# Sch_Kur.net
KiCad netlist of a schematic drawn in Altium Designer
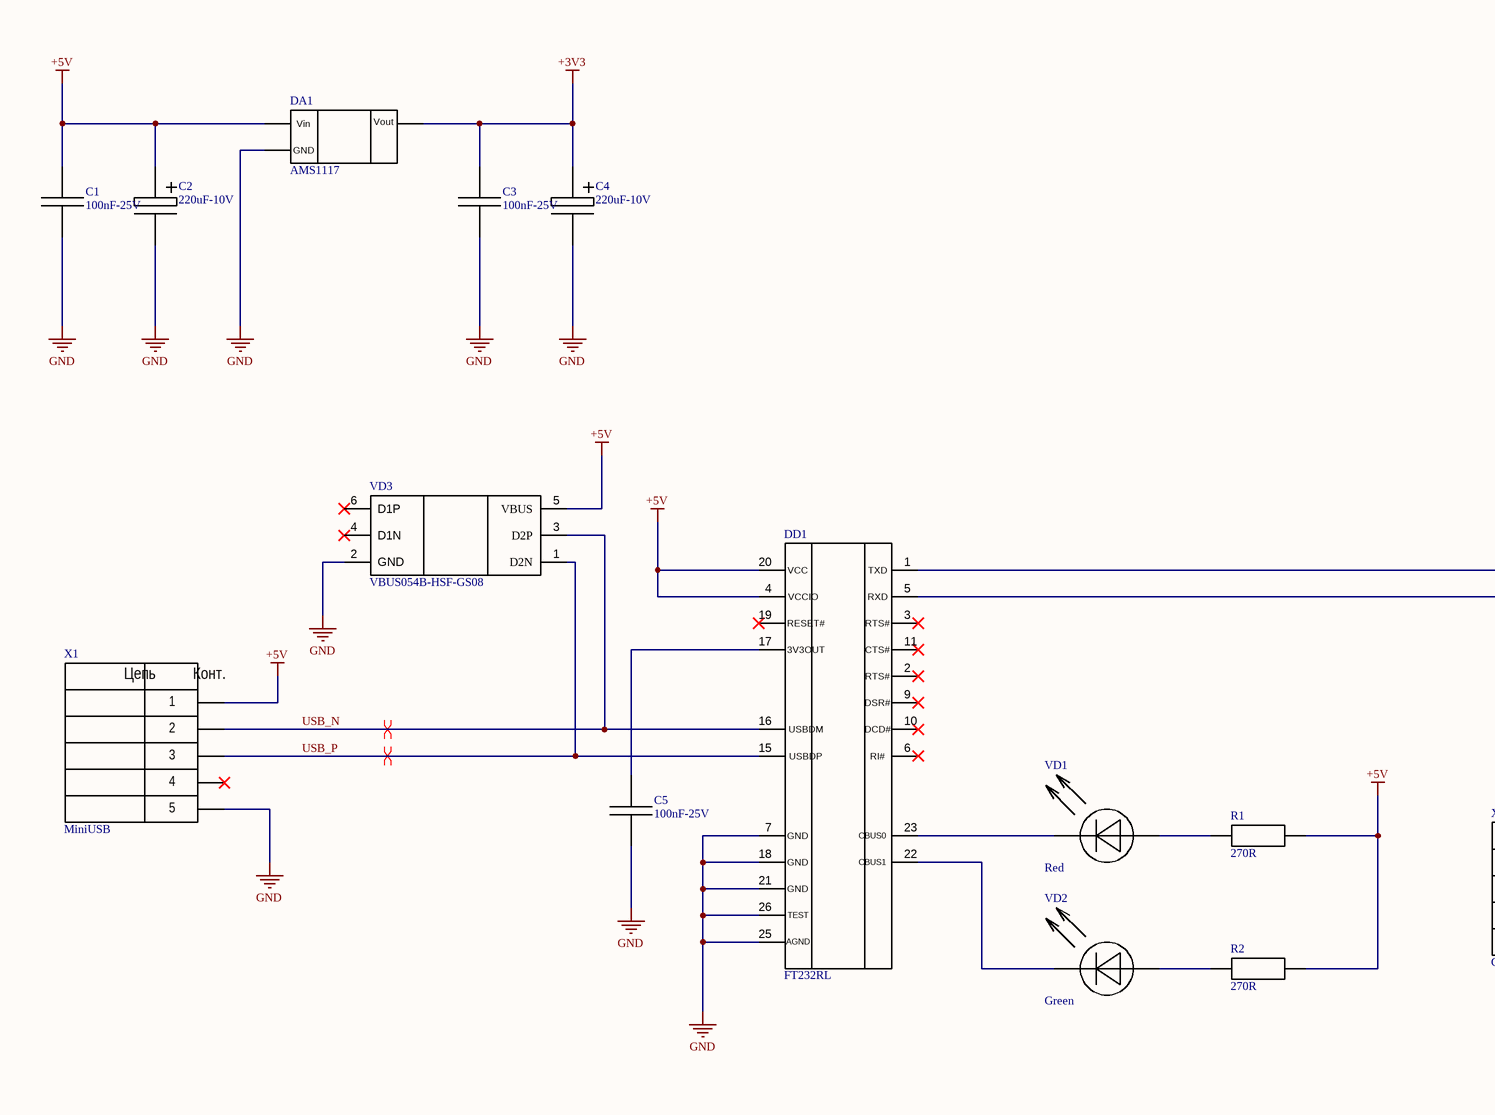
[diagram p0: Sch_Kur.SchDoc, left]
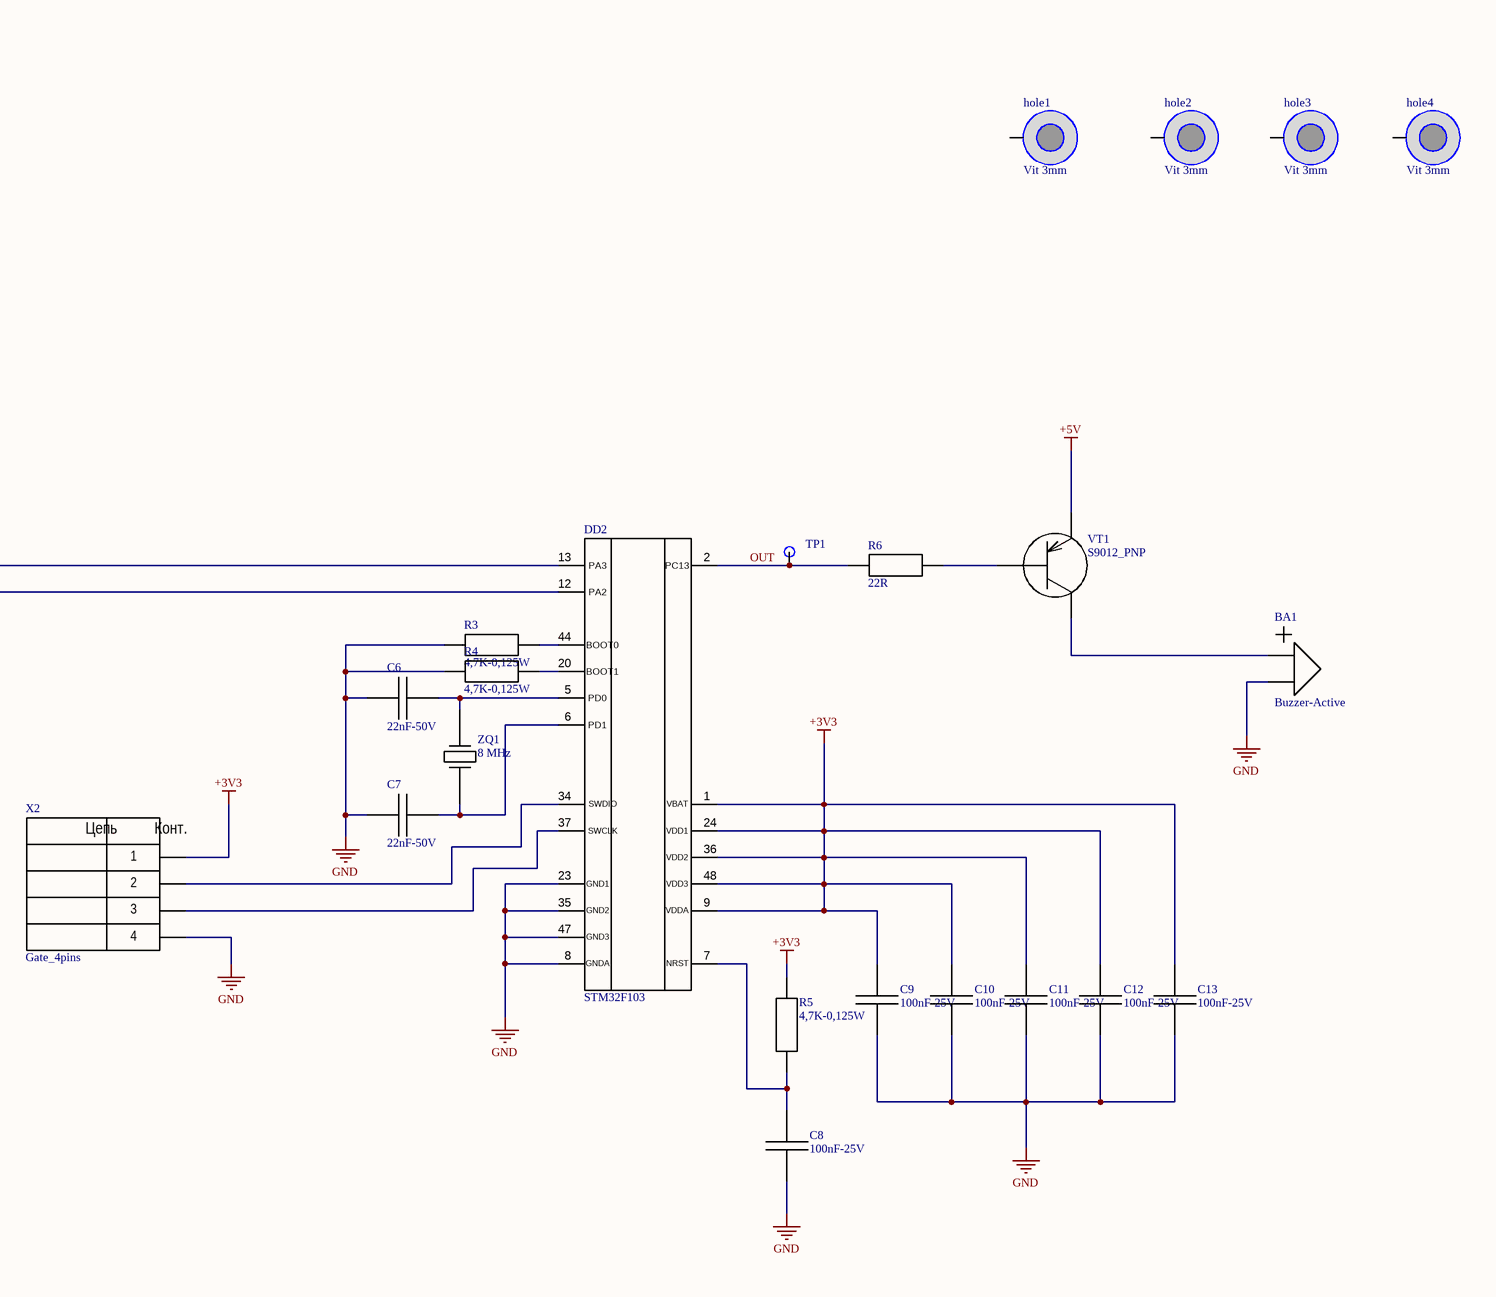
[diagram p1: Sch_Kur.SchDoc, right]

(export (version "E")
  (design (tool "Eeschema 10.0.6"))
  (components
    (comp (ref "BA1")
      (value "Buzzer-Active")
      (footprint "28# Buzzer MINI")
      (libsource (lib "Schlib_Kur") (part "Buzzer"))
    )
    (comp (ref "C1")
      (value "100nF-25V")
      (footprint "Cap Ceramic 0603 SMD")
      (libsource (lib "Schlib_Kur") (part "Cap_100nF"))
    )
    (comp (ref "C2")
      (value "220uF-10V")
      (footprint "CAP ALU CASE E SMD")
      (libsource (lib "Schlib_Kur") (part "ECAP_220uF"))
    )
    (comp (ref "C3")
      (value "100nF-25V")
      (footprint "Cap Ceramic 0603 SMD")
      (libsource (lib "Schlib_Kur") (part "Cap_100nF"))
    )
    (comp (ref "C4")
      (value "220uF-10V")
      (footprint "CAP ALU CASE E SMD")
      (libsource (lib "Schlib_Kur") (part "ECAP_220uF"))
    )
    (comp (ref "C5")
      (value "100nF-25V")
      (footprint "Cap Ceramic 0603 SMD")
      (libsource (lib "Schlib_Kur") (part "Cap_100nF"))
    )
    (comp (ref "C6")
      (value "22nF-50V")
      (footprint "Cap Ceramic 0805 SMD")
      (libsource (lib "Schlib_Kur") (part "Cap_22nF"))
    )
    (comp (ref "C7")
      (value "22nF-50V")
      (footprint "Cap Ceramic 0805 SMD")
      (libsource (lib "Schlib_Kur") (part "Cap_22nF"))
    )
    (comp (ref "C8")
      (value "100nF-25V")
      (footprint "Cap Ceramic 0603 SMD")
      (libsource (lib "Schlib_Kur") (part "Cap_100nF"))
    )
    (comp (ref "C9")
      (value "100nF-25V")
      (footprint "Cap Ceramic 0603 SMD")
      (libsource (lib "Schlib_Kur") (part "Cap_100nF"))
    )
    (comp (ref "C10")
      (value "100nF-25V")
      (footprint "Cap Ceramic 0603 SMD")
      (libsource (lib "Schlib_Kur") (part "Cap_100nF"))
    )
    (comp (ref "C11")
      (value "100nF-25V")
      (footprint "Cap Ceramic 0603 SMD")
      (libsource (lib "Schlib_Kur") (part "Cap_100nF"))
    )
    (comp (ref "C12")
      (value "100nF-25V")
      (footprint "Cap Ceramic 0603 SMD")
      (libsource (lib "Schlib_Kur") (part "Cap_100nF"))
    )
    (comp (ref "C13")
      (value "100nF-25V")
      (footprint "Cap Ceramic 0603 SMD")
      (libsource (lib "Schlib_Kur") (part "Cap_100nF"))
    )
    (comp (ref "DA1")
      (value "AMS1117")
      (footprint "AMS1117-3.3V")
      (libsource (lib "Schlib_Kur") (part "AMS1117-3.3"))
    )
    (comp (ref "DD1") (value "FT232RL") (footprint "SSOP 28") (libsource (lib "Schlib_Kur") (part "FT232RL")))
    (comp (ref "DD2")
      (value "STM32F103")
      (footprint "stm32f103c8t6-48LQFP")
      (libsource (lib "Schlib_Kur") (part "STM32F103C8T6"))
    )
    (comp (ref "hole1")
      (value "Vit 3mm")
      (footprint "Screw 3 small")
      (libsource (lib "lpson") (part "Vit 3mm"))
    )
    (comp (ref "hole2")
      (value "Vit 3mm")
      (footprint "Screw 3 small")
      (libsource (lib "lpson") (part "Vit 3mm"))
    )
    (comp (ref "hole3")
      (value "Vit 3mm")
      (footprint "Screw 3 small")
      (libsource (lib "lpson") (part "Vit 3mm"))
    )
    (comp (ref "hole4")
      (value "Vit 3mm")
      (footprint "Screw 3 small")
      (libsource (lib "lpson") (part "Vit 3mm"))
    )
    (comp (ref "R1") (value "270R") (footprint "Res 0805 SMD") (libsource (lib "") (part "Res_270_1")))
    (comp (ref "R2")
      (value "270R")
      (footprint "Res 0805 SMD")
      (libsource (lib "Schlib_Kur") (part "Res_270"))
    )
    (comp (ref "R3")
      (value "4,7K-0,125W")
      (footprint "Res 0805 SMD")
      (libsource (lib "Schlib_Kur") (part "Res_4K7"))
    )
    (comp (ref "R4")
      (value "4,7K-0,125W")
      (footprint "Res 0805 SMD")
      (libsource (lib "Schlib_Kur") (part "Res_4K7"))
    )
    (comp (ref "R5")
      (value "4,7K-0,125W")
      (footprint "Res 0805 SMD")
      (libsource (lib "Schlib_Kur") (part "Res_4K7"))
    )
    (comp (ref "R6") (value "22R") (footprint "Res 0805 SMD") (libsource (lib "Schlib_Kur") (part "Res_22R")))
    (comp (ref "TP1") (value "TP1") (footprint "TP1") (libsource (lib "Schlib_Kur") (part "Test_point")))
    (comp (ref "VD1") (value "Red") (footprint "Led 0805R") (libsource (lib "Schlib_Kur") (part "LED_red")))
    (comp (ref "VD2")
      (value "Green")
      (footprint "Led 0805G")
      (libsource (lib "Schlib_Kur") (part "LED_green"))
    )
    (comp (ref "VD3")
      (value "VBUS054B-HSF-GS08")
      (footprint "LLP75")
      (libsource (lib "Schlib_Kur") (part "VBUS054B-HSF-GS08"))
    )
    (comp (ref "VT1")
      (value "S9012_PNP")
      (footprint "SOT-23")
      (libsource (lib "Schlib_Kur") (part "Trans_S9012_PNP"))
    )
    (comp (ref "X1")
      (value "MiniUSB")
      (footprint "USB_MNI_B")
      (libsource (lib "Schlib_Kur") (part "Mini_USB"))
    )
    (comp (ref "X2")
      (value "Gate_4pins")
      (footprint "Header_4")
      (libsource (lib "Schlib_Kur") (part "Gate_4pins"))
    )
    (comp (ref "ZQ1")
      (value "8 MHz")
      (footprint "CRYSTAL-HC49S")
      (libsource (lib "Schlib_Kur") (part "Quartz resonator_8MHz"))
    )
  )
  (nets
    (net (code "1") (name "+3V3") (class "Default")
      (node (ref "C10") (pin "2") (pinfunction "2_2") (pintype "passive"))
      (node (ref "C11") (pin "2") (pinfunction "2_2") (pintype "passive"))
      (node (ref "C12") (pin "2") (pinfunction "2_2") (pintype "passive"))
      (node (ref "C13") (pin "2") (pinfunction "2_2") (pintype "passive"))
      (node (ref "C3") (pin "2") (pinfunction "2_2") (pintype "passive"))
      (node (ref "C4") (pin "1") (pinfunction "1_1") (pintype "passive"))
      (node (ref "C9") (pin "2") (pinfunction "2_2") (pintype "passive"))
      (node (ref "DA1") (pin "2") (pinfunction "2_2") (pintype "passive"))
      (node (ref "DD2") (pin "1") (pinfunction "1_1") (pintype "passive"))
      (node (ref "DD2") (pin "24") (pinfunction "24_24") (pintype "passive"))
      (node (ref "DD2") (pin "36") (pinfunction "36_36") (pintype "passive"))
      (node (ref "DD2") (pin "48") (pinfunction "48_48") (pintype "passive"))
      (node (ref "DD2") (pin "9") (pinfunction "9_9") (pintype "passive"))
      (node (ref "R5") (pin "2") (pinfunction "2_2") (pintype "passive"))
      (node (ref "X2") (pin "1") (pintype "passive"))
    )
    (net (code "2") (name "+5V") (class "Default")
      (node (ref "C1") (pin "2") (pinfunction "2_2") (pintype "passive"))
      (node (ref "C2") (pin "1") (pinfunction "1_1") (pintype "passive"))
      (node (ref "DA1") (pin "3") (pinfunction "3_3") (pintype "passive"))
      (node (ref "DD1") (pin "20") (pinfunction "20_20") (pintype "passive"))
      (node (ref "DD1") (pin "4") (pinfunction "4_4") (pintype "passive"))
      (node (ref "R1") (pin "2") (pinfunction "2_2") (pintype "passive"))
      (node (ref "R2") (pin "1") (pinfunction "1_1") (pintype "passive"))
      (node (ref "VD3") (pin "5") (pinfunction "VBUS_5") (pintype "passive"))
      (node (ref "VT1") (pin "2") (pinfunction "2_2") (pintype "passive"))
      (node (ref "X1") (pin "1") (pinfunction "1_1") (pintype "passive"))
    )
    (net (code "3") (name "/OUT") (class "Default")
      (node (ref "DD2") (pin "2") (pinfunction "2_2") (pintype "passive"))
      (node (ref "R6") (pin "1") (pinfunction "1_1") (pintype "passive"))
      (node (ref "TP1") (pin "1") (pinfunction "1_1") (pintype "passive"))
    )
    (net (code "4") (name "/USB_N") (class "Default")
      (node (ref "DD1") (pin "16") (pinfunction "16_16") (pintype "passive"))
      (node (ref "VD3") (pin "3") (pinfunction "D2P_3") (pintype "passive"))
      (node (ref "X1") (pin "2") (pinfunction "2_2") (pintype "passive"))
    )
    (net (code "5") (name "/USB_P") (class "Default")
      (node (ref "DD1") (pin "15") (pinfunction "15_15") (pintype "passive"))
      (node (ref "VD3") (pin "1") (pinfunction "D2N_1") (pintype "passive"))
      (node (ref "X1") (pin "3") (pinfunction "3_3") (pintype "passive"))
    )
    (net (code "6") (name "GND") (class "Default")
      (node (ref "BA1") (pin "2") (pinfunction "2_2") (pintype "passive"))
      (node (ref "C1") (pin "1") (pinfunction "1_1") (pintype "passive"))
      (node (ref "C10") (pin "1") (pinfunction "1_1") (pintype "passive"))
      (node (ref "C11") (pin "1") (pinfunction "1_1") (pintype "passive"))
      (node (ref "C12") (pin "1") (pinfunction "1_1") (pintype "passive"))
      (node (ref "C13") (pin "1") (pinfunction "1_1") (pintype "passive"))
      (node (ref "C2") (pin "2") (pinfunction "2_2") (pintype "passive"))
      (node (ref "C3") (pin "1") (pinfunction "1_1") (pintype "passive"))
      (node (ref "C4") (pin "2") (pinfunction "2_2") (pintype "passive"))
      (node (ref "C5") (pin "1") (pinfunction "1_1") (pintype "passive"))
      (node (ref "C6") (pin "1") (pinfunction "1_1") (pintype "passive"))
      (node (ref "C7") (pin "1") (pinfunction "1_1") (pintype "passive"))
      (node (ref "C8") (pin "1") (pinfunction "1_1") (pintype "passive"))
      (node (ref "C9") (pin "1") (pinfunction "1_1") (pintype "passive"))
      (node (ref "DA1") (pin "1") (pinfunction "1_1") (pintype "passive"))
      (node (ref "DD1") (pin "18") (pinfunction "18_18") (pintype "passive"))
      (node (ref "DD1") (pin "21") (pinfunction "21_21") (pintype "passive"))
      (node (ref "DD1") (pin "25") (pinfunction "25_25") (pintype "passive"))
      (node (ref "DD1") (pin "26") (pinfunction "26_26") (pintype "passive"))
      (node (ref "DD1") (pin "7") (pinfunction "7_7") (pintype "passive"))
      (node (ref "DD2") (pin "23") (pinfunction "23_23") (pintype "passive"))
      (node (ref "DD2") (pin "35") (pinfunction "35_35") (pintype "passive"))
      (node (ref "DD2") (pin "47") (pinfunction "47_47") (pintype "passive"))
      (node (ref "DD2") (pin "8") (pinfunction "8_8") (pintype "passive"))
      (node (ref "R3") (pin "1") (pinfunction "1_1") (pintype "passive"))
      (node (ref "R4") (pin "1") (pinfunction "1_1") (pintype "passive"))
      (node (ref "VD3") (pin "2") (pinfunction "GND_2") (pintype "passive"))
      (node (ref "X1") (pin "5") (pinfunction "5_5") (pintype "passive"))
      (node (ref "X2") (pin "4") (pintype "passive"))
    )
    (net (code "7") (name "Net-(BA1-Pad1)") (class "Default")
      (node (ref "BA1") (pin "1") (pinfunction "1_1") (pintype "passive"))
      (node (ref "VT1") (pin "3") (pinfunction "3_3") (pintype "passive"))
    )
    (net (code "8") (name "Net-(C5-Pad2)") (class "Default")
      (node (ref "C5") (pin "2") (pinfunction "2_2") (pintype "passive"))
      (node (ref "DD1") (pin "17") (pinfunction "17_17") (pintype "passive"))
    )
    (net (code "9") (name "Net-(C6-Pad2)") (class "Default")
      (node (ref "C6") (pin "2") (pinfunction "2_2") (pintype "passive"))
      (node (ref "DD2") (pin "5") (pinfunction "5_5") (pintype "passive"))
      (node (ref "ZQ1") (pin "2") (pinfunction "2_2") (pintype "passive"))
    )
    (net (code "10") (name "Net-(C7-Pad2)") (class "Default")
      (node (ref "C7") (pin "2") (pinfunction "2_2") (pintype "passive"))
      (node (ref "DD2") (pin "6") (pinfunction "6_6") (pintype "passive"))
      (node (ref "ZQ1") (pin "1") (pinfunction "1_1") (pintype "passive"))
    )
    (net (code "11") (name "Net-(C8-Pad2)") (class "Default")
      (node (ref "C8") (pin "2") (pinfunction "2_2") (pintype "passive"))
      (node (ref "DD2") (pin "7") (pinfunction "7_7") (pintype "passive"))
      (node (ref "R5") (pin "1") (pinfunction "1_1") (pintype "passive"))
    )
    (net (code "12") (name "Net-(DD1-Pad1)") (class "Default")
      (node (ref "DD1") (pin "1") (pinfunction "1_1") (pintype "passive"))
      (node (ref "DD2") (pin "13") (pinfunction "13_13") (pintype "passive"))
    )
    (net (code "13") (name "Net-(DD1-Pad5)") (class "Default")
      (node (ref "DD1") (pin "5") (pinfunction "5_5") (pintype "passive"))
      (node (ref "DD2") (pin "12") (pinfunction "12_12") (pintype "passive"))
    )
    (net (code "14") (name "Net-(DD1-Pad22)") (class "Default")
      (node (ref "DD1") (pin "22") (pinfunction "22_22") (pintype "passive"))
      (node (ref "VD2") (pin "2") (pinfunction "2_2") (pintype "passive"))
    )
    (net (code "15") (name "Net-(DD1-Pad23)") (class "Default")
      (node (ref "DD1") (pin "23") (pinfunction "23_23") (pintype "passive"))
      (node (ref "VD1") (pin "2") (pinfunction "2_2") (pintype "passive"))
    )
    (net (code "16") (name "Net-(DD2-Pad20)") (class "Default")
      (node (ref "DD2") (pin "20") (pinfunction "20_20") (pintype "passive"))
      (node (ref "R4") (pin "2") (pinfunction "2_2") (pintype "passive"))
    )
    (net (code "17") (name "Net-(DD2-Pad34)") (class "Default")
      (node (ref "DD2") (pin "34") (pinfunction "34_34") (pintype "passive"))
      (node (ref "X2") (pin "2") (pintype "passive"))
    )
    (net (code "18") (name "Net-(DD2-Pad37)") (class "Default")
      (node (ref "DD2") (pin "37") (pinfunction "37_37") (pintype "passive"))
      (node (ref "X2") (pin "3") (pintype "passive"))
    )
    (net (code "19") (name "Net-(DD2-Pad44)") (class "Default")
      (node (ref "DD2") (pin "44") (pinfunction "44_44") (pintype "passive"))
      (node (ref "R3") (pin "2") (pinfunction "2_2") (pintype "passive"))
    )
    (net (code "20") (name "Net-(R1-Pad1)") (class "Default")
      (node (ref "R1") (pin "1") (pinfunction "1_1") (pintype "passive"))
      (node (ref "VD1") (pin "1") (pinfunction "1_1") (pintype "passive"))
    )
    (net (code "21") (name "Net-(R2-Pad2)") (class "Default")
      (node (ref "R2") (pin "2") (pinfunction "2_2") (pintype "passive"))
      (node (ref "VD2") (pin "1") (pinfunction "1_1") (pintype "passive"))
    )
    (net (code "22") (name "Net-(R6-Pad2)") (class "Default")
      (node (ref "R6") (pin "2") (pinfunction "2_2") (pintype "passive"))
      (node (ref "VT1") (pin "1") (pinfunction "1_1") (pintype "passive"))
    )
    (net (code "23") (name "unconnected-(DD1-Pad2)") (class "Default")
      (node (ref "DD1") (pin "2") (pinfunction "2_2") (pintype "passive+no_connect"))
    )
    (net (code "24") (name "unconnected-(DD1-Pad3)") (class "Default")
      (node (ref "DD1") (pin "3") (pinfunction "3_3") (pintype "passive+no_connect"))
    )
    (net (code "25") (name "unconnected-(DD1-Pad6)") (class "Default")
      (node (ref "DD1") (pin "6") (pinfunction "6_6") (pintype "passive+no_connect"))
    )
    (net (code "26") (name "unconnected-(DD1-Pad9)") (class "Default")
      (node (ref "DD1") (pin "9") (pinfunction "9_9") (pintype "passive+no_connect"))
    )
    (net (code "27") (name "unconnected-(DD1-Pad10)") (class "Default")
      (node (ref "DD1") (pin "10") (pinfunction "10_10") (pintype "passive+no_connect"))
    )
    (net (code "28") (name "unconnected-(DD1-Pad11)") (class "Default")
      (node (ref "DD1") (pin "11") (pinfunction "11_11") (pintype "passive+no_connect"))
    )
    (net (code "29") (name "unconnected-(DD1-Pad19)") (class "Default")
      (node (ref "DD1") (pin "19") (pinfunction "19_19") (pintype "passive+no_connect"))
    )
    (net (code "30") (name "unconnected-(VD3-D1N-Pad4)") (class "Default")
      (node (ref "VD3") (pin "4") (pinfunction "D1N_4") (pintype "passive+no_connect"))
    )
    (net (code "31") (name "unconnected-(VD3-D1P-Pad6)") (class "Default")
      (node (ref "VD3") (pin "6") (pinfunction "D1P_6") (pintype "passive+no_connect"))
    )
    (net (code "32") (name "unconnected-(X1-Pad4)") (class "Default")
      (node (ref "X1") (pin "4") (pinfunction "4_4") (pintype "passive+no_connect"))
    )
    (net (code "33") (name "unconnected-(hole1-hole-Pad1)") (class "Default")
      (node (ref "hole1") (pin "1") (pinfunction "hole_1") (pintype "passive"))
    )
    (net (code "34") (name "unconnected-(hole2-hole-Pad1)") (class "Default")
      (node (ref "hole2") (pin "1") (pinfunction "hole_1") (pintype "passive"))
    )
    (net (code "35") (name "unconnected-(hole3-hole-Pad1)") (class "Default")
      (node (ref "hole3") (pin "1") (pinfunction "hole_1") (pintype "passive"))
    )
    (net (code "36") (name "unconnected-(hole4-hole-Pad1)") (class "Default")
      (node (ref "hole4") (pin "1") (pinfunction "hole_1") (pintype "passive"))
    )
  )
)
